# Button.net
KiCad netlist of a schematic drawn in EAGLE
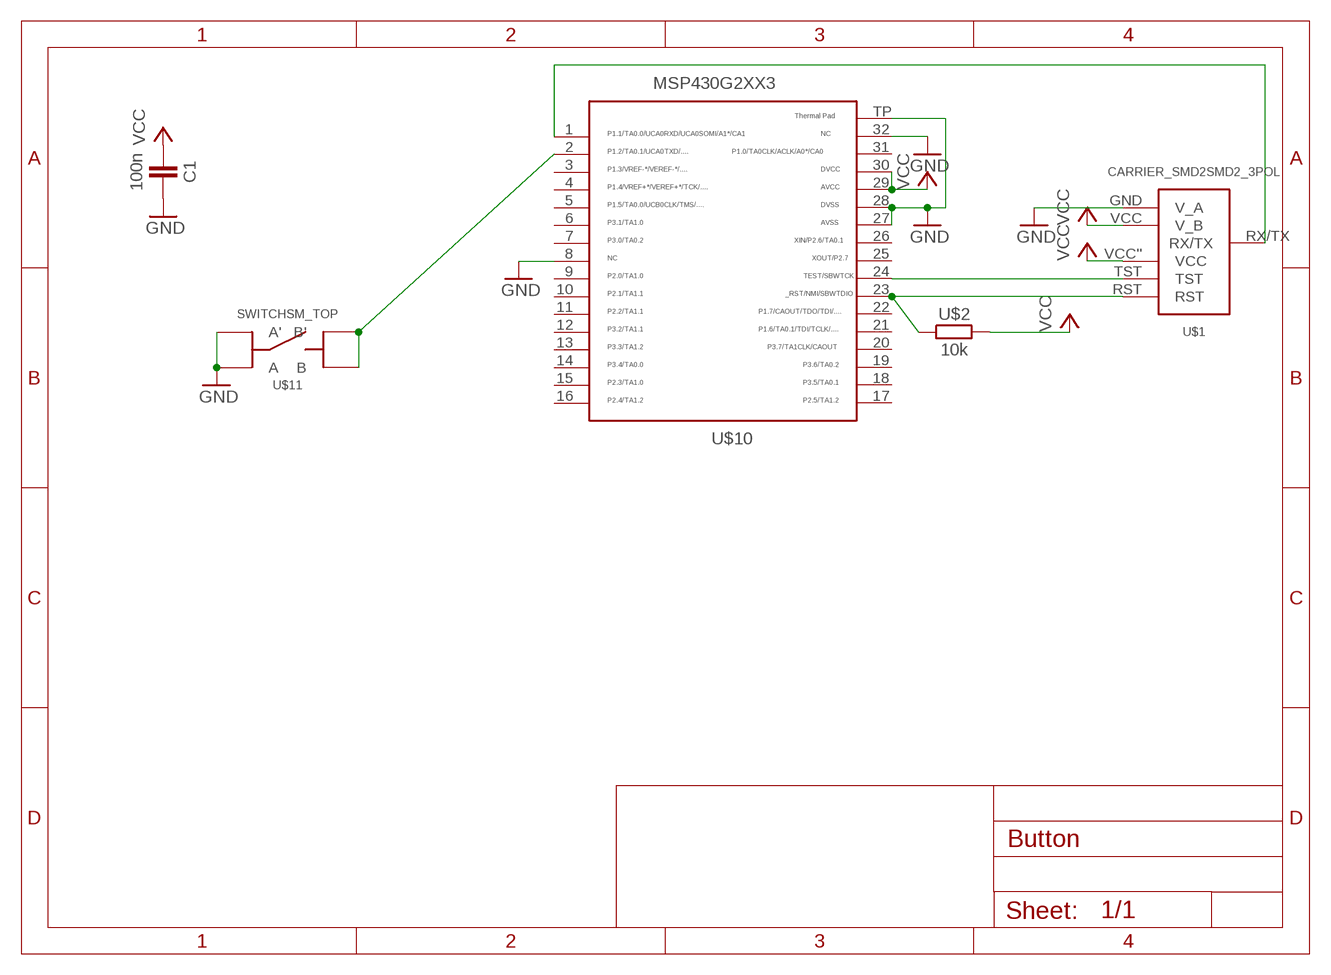
[diagram p0: schematic, sheet 1]

(export (version "E")
  (design (tool "Eeschema 10.0.6"))
  (components
    (comp (ref "C1")
      (value "100n")
      (footprint "eagle-import:603")
      (libsource (lib "eagle-import") (part "CAPACITOR"))
    )
    (comp (ref "U$1")
      (value "CARRIER_SMD2SMD2_3POL")
      (footprint "eagle-import:CARRIER_SMD2_3POL")
      (libsource (lib "eagle-import") (part "CARRIER_SMD2SMD2_3POL"))
    )
    (comp (ref "U$2")
      (value "10k")
      (footprint "eagle-import:603")
      (libsource (lib "eagle-import") (part "RESISTOR0603"))
    )
    (comp (ref "U$10")
      (value "MSP430G2553")
      (footprint "eagle-import:QFN32")
      (libsource (lib "eagle-import") (part "MSP430G2553"))
    )
    (comp (ref "U$11")
      (value "SWITCHSM_TOP")
      (footprint "eagle-import:BUTTON_SMD")
      (libsource (lib "eagle-import") (part "SWITCHSM_TOP"))
    )
  )
  (nets
    (net (code "1") (name "GND") (class "Default")
      (node (ref "C1") (pin "2") (pinfunction "2_2") (pintype "passive"))
      (node (ref "U$1") (pin "GND") (pinfunction "V_A_GND") (pintype "bidirectional"))
      (node (ref "U$10") (pin "27") (pinfunction "27_27") (pintype "bidirectional"))
      (node (ref "U$10") (pin "28") (pinfunction "28_28") (pintype "bidirectional"))
      (node (ref "U$10") (pin "32") (pinfunction "32_32") (pintype "bidirectional"))
      (node (ref "U$10") (pin "8") (pinfunction "8_8") (pintype "bidirectional"))
      (node (ref "U$10") (pin "TP") (pinfunction "TP_TP") (pintype "bidirectional"))
      (node (ref "U$11") (pin "1") (pinfunction "A_1") (pintype "bidirectional"))
      (node (ref "U$11") (pin "2") (pinfunction "A'_2") (pintype "bidirectional"))
    )
    (net (code "2") (name "Net-(U$1-PadRST)") (class "Default")
      (node (ref "U$1") (pin "RST") (pinfunction "RST_RST") (pintype "bidirectional"))
      (node (ref "U$10") (pin "23") (pinfunction "23_23") (pintype "bidirectional"))
      (node (ref "U$2") (pin "1") (pinfunction "1_1") (pintype "passive"))
    )
    (net (code "3") (name "Net-(U$1-PadRX{slash}TX)") (class "Default")
      (node (ref "U$1") (pin "RX/TX") (pinfunction "RX/TX_RX/TX") (pintype "bidirectional"))
      (node (ref "U$10") (pin "1") (pinfunction "1_1") (pintype "bidirectional"))
    )
    (net (code "4") (name "Net-(U$1-PadTST)") (class "Default")
      (node (ref "U$1") (pin "TST") (pinfunction "TST_TST") (pintype "bidirectional"))
      (node (ref "U$10") (pin "24") (pinfunction "24_24") (pintype "bidirectional"))
    )
    (net (code "5") (name "Net-(U$11-B')") (class "Default")
      (node (ref "U$10") (pin "2") (pinfunction "2_2") (pintype "bidirectional"))
      (node (ref "U$11") (pin "3") (pinfunction "B_3") (pintype "bidirectional"))
      (node (ref "U$11") (pin "4") (pinfunction "B'_4") (pintype "bidirectional"))
    )
    (net (code "6") (name "VCC") (class "Default")
      (node (ref "C1") (pin "1") (pinfunction "1_1") (pintype "passive"))
      (node (ref "U$1") (pin "VCC") (pinfunction "V_B_VCC") (pintype "bidirectional"))
      (node (ref "U$1") (pin "VCC''") (pinfunction "VCC_VCC''") (pintype "bidirectional"))
      (node (ref "U$10") (pin "29") (pinfunction "29_29") (pintype "bidirectional"))
      (node (ref "U$10") (pin "30") (pinfunction "30_30") (pintype "bidirectional"))
      (node (ref "U$2") (pin "2") (pinfunction "2_2") (pintype "passive"))
    )
    (net (code "7") (name "unconnected-(U$10-Pad3)") (class "Default")
      (node (ref "U$10") (pin "3") (pinfunction "3_3") (pintype "bidirectional"))
    )
    (net (code "8") (name "unconnected-(U$10-Pad4)") (class "Default")
      (node (ref "U$10") (pin "4") (pinfunction "4_4") (pintype "bidirectional"))
    )
    (net (code "9") (name "unconnected-(U$10-Pad5)") (class "Default")
      (node (ref "U$10") (pin "5") (pinfunction "5_5") (pintype "bidirectional"))
    )
    (net (code "10") (name "unconnected-(U$10-Pad6)") (class "Default")
      (node (ref "U$10") (pin "6") (pinfunction "6_6") (pintype "bidirectional"))
    )
    (net (code "11") (name "unconnected-(U$10-Pad7)") (class "Default")
      (node (ref "U$10") (pin "7") (pinfunction "7_7") (pintype "bidirectional"))
    )
    (net (code "12") (name "unconnected-(U$10-Pad9)") (class "Default")
      (node (ref "U$10") (pin "9") (pinfunction "9_9") (pintype "bidirectional"))
    )
    (net (code "13") (name "unconnected-(U$10-Pad10)") (class "Default")
      (node (ref "U$10") (pin "10") (pinfunction "10_10") (pintype "bidirectional"))
    )
    (net (code "14") (name "unconnected-(U$10-Pad11)") (class "Default")
      (node (ref "U$10") (pin "11") (pinfunction "11_11") (pintype "bidirectional"))
    )
    (net (code "15") (name "unconnected-(U$10-Pad12)") (class "Default")
      (node (ref "U$10") (pin "12") (pinfunction "12_12") (pintype "bidirectional"))
    )
    (net (code "16") (name "unconnected-(U$10-Pad13)") (class "Default")
      (node (ref "U$10") (pin "13") (pinfunction "13_13") (pintype "bidirectional"))
    )
    (net (code "17") (name "unconnected-(U$10-Pad14)") (class "Default")
      (node (ref "U$10") (pin "14") (pinfunction "14_14") (pintype "bidirectional"))
    )
    (net (code "18") (name "unconnected-(U$10-Pad15)") (class "Default")
      (node (ref "U$10") (pin "15") (pinfunction "15_15") (pintype "bidirectional"))
    )
    (net (code "19") (name "unconnected-(U$10-Pad16)") (class "Default")
      (node (ref "U$10") (pin "16") (pinfunction "16_16") (pintype "bidirectional"))
    )
    (net (code "20") (name "unconnected-(U$10-Pad17)") (class "Default")
      (node (ref "U$10") (pin "17") (pinfunction "17_17") (pintype "bidirectional"))
    )
    (net (code "21") (name "unconnected-(U$10-Pad18)") (class "Default")
      (node (ref "U$10") (pin "18") (pinfunction "18_18") (pintype "bidirectional"))
    )
    (net (code "22") (name "unconnected-(U$10-Pad19)") (class "Default")
      (node (ref "U$10") (pin "19") (pinfunction "19_19") (pintype "bidirectional"))
    )
    (net (code "23") (name "unconnected-(U$10-Pad20)") (class "Default")
      (node (ref "U$10") (pin "20") (pinfunction "20_20") (pintype "bidirectional"))
    )
    (net (code "24") (name "unconnected-(U$10-Pad21)") (class "Default")
      (node (ref "U$10") (pin "21") (pinfunction "21_21") (pintype "bidirectional"))
    )
    (net (code "25") (name "unconnected-(U$10-Pad22)") (class "Default")
      (node (ref "U$10") (pin "22") (pinfunction "22_22") (pintype "bidirectional"))
    )
    (net (code "26") (name "unconnected-(U$10-Pad25)") (class "Default")
      (node (ref "U$10") (pin "25") (pinfunction "25_25") (pintype "bidirectional"))
    )
    (net (code "27") (name "unconnected-(U$10-Pad26)") (class "Default")
      (node (ref "U$10") (pin "26") (pinfunction "26_26") (pintype "bidirectional"))
    )
    (net (code "28") (name "unconnected-(U$10-Pad31)") (class "Default")
      (node (ref "U$10") (pin "31") (pinfunction "31_31") (pintype "bidirectional"))
    )
  )
)
